# L1S2.net
KiCad netlist of a schematic drawn in Altium Designer
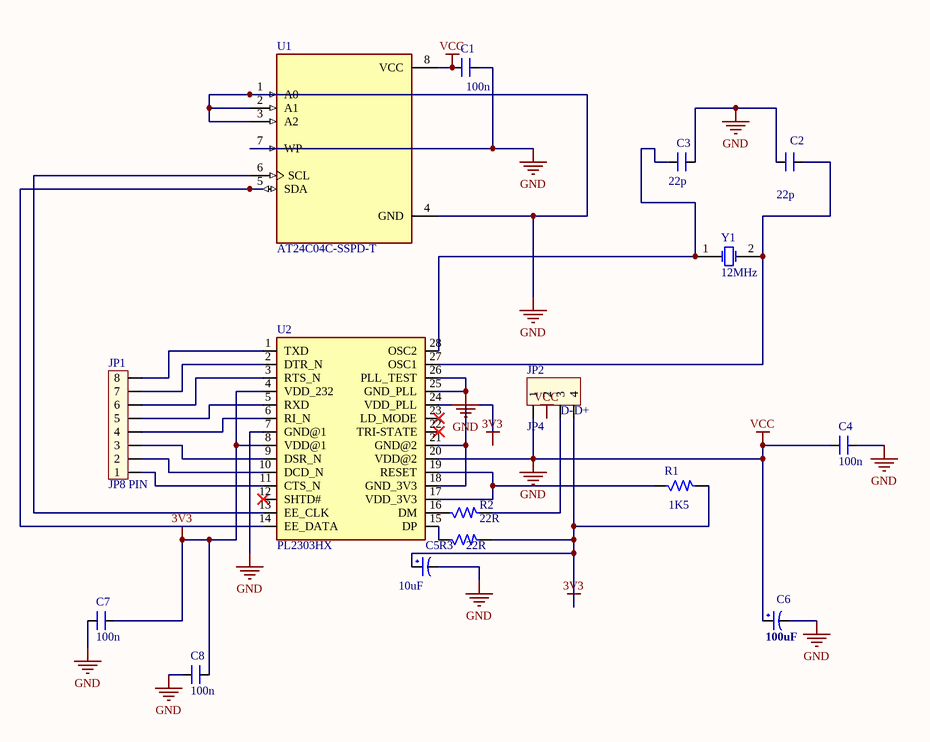
[diagram p0: L1S2.SchDoc]

(export (version "E")
  (design (tool "Eeschema 10.0.6"))
  (components
    (comp (ref "C1")
      (value "100n")
      (footprint "0805_Cap")
      (description "Cap SMD")
      (libsource (lib "HaiThai") (part "CM"))
    )
    (comp (ref "C2")
      (value "22p")
      (footprint "0805_Cap")
      (description "Cap SMD")
      (libsource (lib "HaiThai") (part "CM"))
    )
    (comp (ref "C3")
      (value "22p")
      (footprint "0805_Cap")
      (description "Cap SMD")
      (libsource (lib "HaiThai") (part "CM"))
    )
    (comp (ref "C4")
      (value "100n")
      (footprint "0805_Cap")
      (description "Cap SMD")
      (libsource (lib "HaiThai") (part "CM"))
    )
    (comp (ref "C5")
      (value "10uF")
      (footprint "CP1/2.5")
      (description "C 47uF/50V , 220uF/16V")
      (libsource (lib "HaiThai") (part "CP2"))
    )
    (comp (ref "C6")
      (value "100uF")
      (footprint "CP1/2.5")
      (description "C 47uF/50V , 220uF/16V")
      (libsource (lib "HaiThai") (part "CP2"))
    )
    (comp (ref "C7")
      (value "100n")
      (footprint "0805_Cap")
      (description "Cap SMD")
      (libsource (lib "HaiThai") (part "CM"))
    )
    (comp (ref "C8")
      (value "100n")
      (footprint "0805_Cap")
      (description "Cap SMD")
      (libsource (lib "HaiThai") (part "CM"))
    )
    (comp (ref "JP1") (value "JP8 PIN") (footprint "JP8") (libsource (lib "HaiThai") (part "JP8")))
    (comp (ref "JP2")
      (value "JP4")
      (footprint "CON4")
      (description "Connector 4")
      (libsource (lib "HaiThai") (part "Con4"))
    )
    (comp (ref "R1")
      (value "1K5")
      (footprint "0402_res")
      (description "Resistor 1/4W")
      (libsource (lib "HaiThai") (part "R"))
    )
    (comp (ref "R2")
      (value "22R")
      (footprint "0402_res")
      (description "Resistor 1/4W")
      (libsource (lib "HaiThai") (part "R"))
    )
    (comp (ref "R3")
      (value "22R")
      (footprint "0402_res")
      (description "Resistor 1/4W")
      (libsource (lib "HaiThai") (part "R"))
    )
    (comp (ref "U1")
      (value "AT24C04C-SSPD-T")
      (footprint "SOIC127P600X175-8N")
      (description "EEPROM Memory IC 4Kb _512 x 8_ IÂ²C 400kHz 900ns 8-SOIC")
      (fields (field (name "MF") "Microchip Technology"))
      (libsource (lib "AT24C04C-SSPD-T") (part "AT24C04C-SSPD-T"))
    )
    (comp (ref "U2")
      (value "PL2303HX")
      (footprint "TSSOP28")
      (description "USB to RS232 TSSOP28")
      (fields (field (name "MF") "Prolific Technology") (field (name "MP") "PL-2303HX"))
      (libsource (lib "PL2303HX") (part "PL2303HX"))
    )
    (comp (ref "Y1")
      (value "12MHz")
      (footprint "XT2")
      (description "Crystal Oscillator")
      (fields (field (name "PUBLISHER") "Altium Limited"))
      (libsource (lib "HaiThai") (part "XTAL"))
    )
  )
  (nets
    (net (code "1") (name "3V3") (class "Default")
      (node (ref "C5") (pin "1") (pinfunction "1_1") (pintype "passive"))
      (node (ref "C7") (pin "2") (pinfunction "2_2") (pintype "passive"))
      (node (ref "C8") (pin "2") (pinfunction "2_2") (pintype "passive"))
      (node (ref "JP2") (pin "4") (pinfunction "4_4") (pintype "passive"))
      (node (ref "R1") (pin "2") (pinfunction "2_2") (pintype "passive"))
      (node (ref "R3") (pin "2") (pinfunction "2_2") (pintype "passive"))
      (node (ref "U2") (pin "24") (pinfunction "VDD_PLL_24") (pintype "bidirectional"))
      (node (ref "U2") (pin "4") (pinfunction "VDD_232_4") (pintype "bidirectional"))
      (node (ref "U2") (pin "8") (pinfunction "VDD@1_8") (pintype "bidirectional"))
    )
    (net (code "2") (name "GND") (class "Default")
      (node (ref "C1") (pin "1") (pinfunction "1_1") (pintype "passive"))
      (node (ref "C1") (pin "2") (pinfunction "2_2") (pintype "passive"))
      (node (ref "C2") (pin "1") (pinfunction "1_1") (pintype "passive"))
      (node (ref "C3") (pin "2") (pinfunction "2_2") (pintype "passive"))
      (node (ref "C4") (pin "1") (pinfunction "1_1") (pintype "passive"))
      (node (ref "C4") (pin "2") (pinfunction "2_2") (pintype "passive"))
      (node (ref "C5") (pin "2") (pinfunction "2_2") (pintype "passive"))
      (node (ref "C6") (pin "1") (pinfunction "1_1") (pintype "passive"))
      (node (ref "C6") (pin "2") (pinfunction "2_2") (pintype "passive"))
      (node (ref "C7") (pin "1") (pinfunction "1_1") (pintype "passive"))
      (node (ref "C8") (pin "1") (pinfunction "1_1") (pintype "passive"))
      (node (ref "JP2") (pin "1") (pinfunction "1_1") (pintype "passive"))
      (node (ref "JP2") (pin "2") (pinfunction "2_2") (pintype "passive"))
      (node (ref "U1") (pin "1") (pinfunction "A0_1") (pintype "input"))
      (node (ref "U1") (pin "2") (pinfunction "A1_2") (pintype "input"))
      (node (ref "U1") (pin "3") (pinfunction "A2_3") (pintype "input"))
      (node (ref "U1") (pin "4") (pinfunction "GND_4") (pintype "power_in"))
      (node (ref "U1") (pin "7") (pinfunction "WP_7") (pintype "input"))
      (node (ref "U1") (pin "8") (pinfunction "VCC_8") (pintype "power_in"))
      (node (ref "U2") (pin "18") (pinfunction "GND_3V3_18") (pintype "bidirectional"))
      (node (ref "U2") (pin "20") (pinfunction "VDD@2_20") (pintype "bidirectional"))
      (node (ref "U2") (pin "21") (pinfunction "GND@2_21") (pintype "bidirectional"))
      (node (ref "U2") (pin "25") (pinfunction "GND_PLL_25") (pintype "bidirectional"))
      (node (ref "U2") (pin "26") (pinfunction "PLL_TEST_26") (pintype "bidirectional"))
      (node (ref "U2") (pin "7") (pinfunction "GND@1_7") (pintype "bidirectional"))
    )
    (net (code "3") (name "Net-(JP2-Pad3)") (class "Default")
      (node (ref "JP2") (pin "3") (pinfunction "3_3") (pintype "passive"))
      (node (ref "R2") (pin "2") (pinfunction "2_2") (pintype "passive"))
    )
    (net (code "4") (name "Net-(U1-SCL)") (class "Default")
      (node (ref "U1") (pin "6") (pinfunction "SCL_6") (pintype "input"))
      (node (ref "U2") (pin "13") (pinfunction "EE_CLK_13") (pintype "bidirectional"))
    )
    (net (code "5") (name "Net-(U1-SDA)") (class "Default")
      (node (ref "U1") (pin "5") (pinfunction "SDA_5") (pintype "bidirectional"))
      (node (ref "U2") (pin "14") (pinfunction "EE_DATA_14") (pintype "bidirectional"))
    )
    (net (code "6") (name "Net-(U2-CTS_N)") (class "Default")
      (node (ref "JP1") (pin "1") (pinfunction "1_1") (pintype "passive"))
      (node (ref "U2") (pin "11") (pinfunction "CTS_N_11") (pintype "bidirectional"))
    )
    (net (code "7") (name "Net-(U2-DCD_N)") (class "Default")
      (node (ref "JP1") (pin "2") (pinfunction "2_2") (pintype "passive"))
      (node (ref "U2") (pin "10") (pinfunction "DCD_N_10") (pintype "bidirectional"))
    )
    (net (code "8") (name "Net-(U2-DM)") (class "Default")
      (node (ref "R2") (pin "1") (pinfunction "1_1") (pintype "passive"))
      (node (ref "U2") (pin "16") (pinfunction "DM_16") (pintype "bidirectional"))
    )
    (net (code "9") (name "Net-(U2-DP)") (class "Default")
      (node (ref "R3") (pin "1") (pinfunction "1_1") (pintype "passive"))
      (node (ref "U2") (pin "15") (pinfunction "DP_15") (pintype "bidirectional"))
    )
    (net (code "10") (name "Net-(U2-DSR_N)") (class "Default")
      (node (ref "JP1") (pin "3") (pinfunction "3_3") (pintype "passive"))
      (node (ref "U2") (pin "9") (pinfunction "DSR_N_9") (pintype "bidirectional"))
    )
    (net (code "11") (name "Net-(U2-DTR_N)") (class "Default")
      (node (ref "JP1") (pin "7") (pinfunction "7_7") (pintype "passive"))
      (node (ref "U2") (pin "2") (pinfunction "DTR_N_2") (pintype "bidirectional"))
    )
    (net (code "12") (name "Net-(U2-OSC1)") (class "Default")
      (node (ref "C2") (pin "2") (pinfunction "2_2") (pintype "passive"))
      (node (ref "U2") (pin "27") (pinfunction "OSC1_27") (pintype "bidirectional"))
      (node (ref "Y1") (pin "2") (pinfunction "OSC2_2") (pintype "passive"))
    )
    (net (code "13") (name "Net-(U2-OSC2)") (class "Default")
      (node (ref "C3") (pin "1") (pinfunction "1_1") (pintype "passive"))
      (node (ref "U2") (pin "28") (pinfunction "OSC2_28") (pintype "bidirectional"))
      (node (ref "Y1") (pin "1") (pinfunction "OSC1_1") (pintype "passive"))
    )
    (net (code "14") (name "Net-(U2-RESET)") (class "Default")
      (node (ref "R1") (pin "1") (pinfunction "1_1") (pintype "passive"))
      (node (ref "U2") (pin "17") (pinfunction "VDD_3V3_17") (pintype "bidirectional"))
      (node (ref "U2") (pin "19") (pinfunction "RESET_19") (pintype "bidirectional"))
    )
    (net (code "15") (name "Net-(U2-RI_N)") (class "Default")
      (node (ref "JP1") (pin "4") (pinfunction "4_4") (pintype "passive"))
      (node (ref "U2") (pin "6") (pinfunction "RI_N_6") (pintype "bidirectional"))
    )
    (net (code "16") (name "Net-(U2-RTS_N)") (class "Default")
      (node (ref "JP1") (pin "6") (pinfunction "6_6") (pintype "passive"))
      (node (ref "U2") (pin "3") (pinfunction "RTS_N_3") (pintype "bidirectional"))
    )
    (net (code "17") (name "Net-(U2-RXD)") (class "Default")
      (node (ref "JP1") (pin "5") (pinfunction "5_5") (pintype "passive"))
      (node (ref "U2") (pin "5") (pinfunction "RXD_5") (pintype "bidirectional"))
    )
    (net (code "18") (name "Net-(U2-TXD)") (class "Default")
      (node (ref "JP1") (pin "8") (pinfunction "8_8") (pintype "passive"))
      (node (ref "U2") (pin "1") (pinfunction "TXD_1") (pintype "bidirectional"))
    )
    (net (code "19") (name "unconnected-(U2-LD_MODE-Pad23)") (class "Default")
      (node (ref "U2") (pin "23") (pinfunction "LD_MODE_23") (pintype "bidirectional+no_connect"))
    )
    (net (code "20") (name "unconnected-(U2-SHTD#-Pad12)") (class "Default")
      (node (ref "U2") (pin "12") (pinfunction "SHTD#_12") (pintype "bidirectional+no_connect"))
    )
    (net (code "21") (name "unconnected-(U2-TRI-STATE-Pad22)") (class "Default")
      (node (ref "U2") (pin "22") (pinfunction "TRI-STATE_22") (pintype "bidirectional+no_connect"))
    )
  )
)
